# lvco-1S.net
KiCad netlist of a schematic drawn in EAGLE
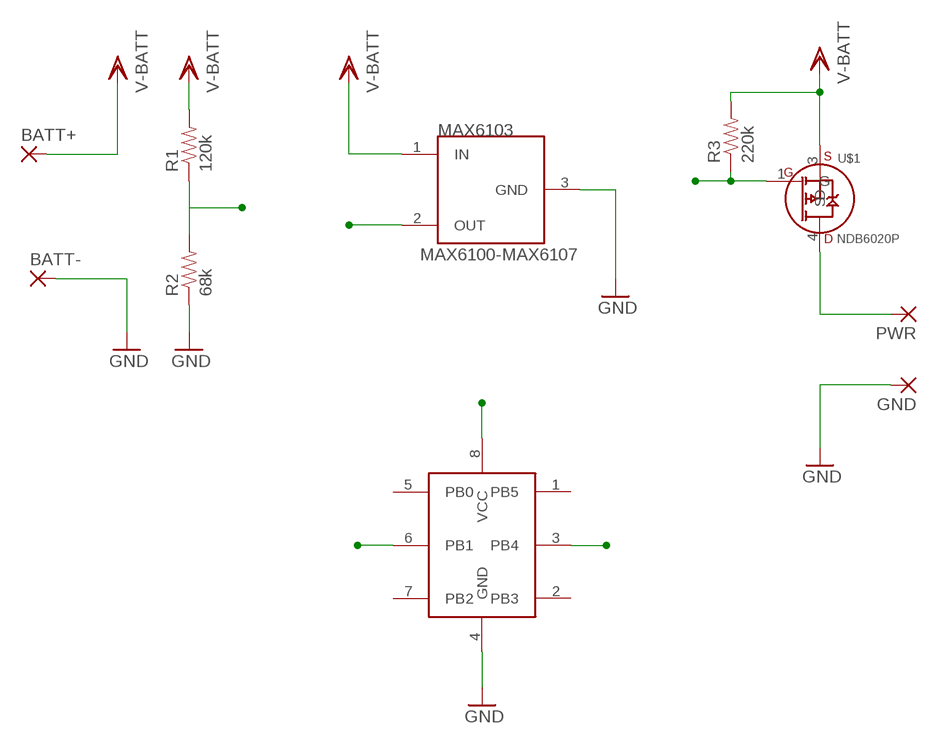
[diagram p0: schematic, sheet 1]

(export (version "E")
  (design (tool "Eeschema 10.0.6"))
  (components
    (comp (ref "BATT+")
      (value "WIREPAD2,54/1,1")
      (footprint "eagle-import:2,54_1,1")
      (libsource (lib "eagle-import") (part "WIREPAD2,54/1,1"))
    )
    (comp (ref "BATT-")
      (value "WIREPAD2,54/1,1")
      (footprint "eagle-import:2,54_1,1")
      (libsource (lib "eagle-import") (part "WIREPAD2,54/1,1"))
    )
    (comp (ref "GND")
      (value "WIREPAD2,54/1,1")
      (footprint "eagle-import:2,54_1,1")
      (libsource (lib "eagle-import") (part "WIREPAD2,54/1,1"))
    )
    (comp (ref "MAX6103")
      (value "MAX6100-MAX6107")
      (footprint "eagle-import:SOT-23-3")
      (libsource (lib "eagle-import") (part "MAX6100-MAX6107"))
    )
    (comp (ref "PWR")
      (value "WIREPAD2,54/1,1")
      (footprint "eagle-import:2,54_1,1")
      (libsource (lib "eagle-import") (part "WIREPAD2,54/1,1"))
    )
    (comp (ref "R1")
      (value "120k")
      (footprint "eagle-import:0805")
      (libsource (lib "eagle-import") (part "RESISTOR0805-RES"))
    )
    (comp (ref "R2")
      (value "68k")
      (footprint "eagle-import:0805")
      (libsource (lib "eagle-import") (part "RESISTOR0805-RES"))
    )
    (comp (ref "R3")
      (value "220k")
      (footprint "eagle-import:0805")
      (libsource (lib "eagle-import") (part "RESISTOR0805-RES"))
    )
    (comp (ref "U$1")
      (value "NDB6020P")
      (footprint "eagle-import:TO-263AB")
      (libsource (lib "eagle-import") (part "NDB6020P"))
    )
    (comp (ref "U$2")
      (value "ATTINY13")
      (footprint "eagle-import:WSOIC-8")
      (libsource (lib "eagle-import") (part "ATTINY13"))
    )
  )
  (nets
    (net (code "1") (name "/REF-BATT") (class "Default")
      (node (ref "R1") (pin "1") (pinfunction "1_1") (pintype "passive"))
      (node (ref "R2") (pin "2") (pinfunction "2_2") (pintype "passive"))
      (node (ref "U$2") (pin "6") (pinfunction "PB1_6") (pintype "bidirectional"))
    )
    (net (code "2") (name "/SW") (class "Default")
      (node (ref "R3") (pin "1") (pinfunction "1_1") (pintype "passive"))
      (node (ref "U$1") (pin "1") (pinfunction "G_1") (pintype "bidirectional"))
      (node (ref "U$2") (pin "3") (pinfunction "PB4_3") (pintype "bidirectional"))
    )
    (net (code "3") (name "/VCC") (class "Default")
      (node (ref "MAX6103") (pin "2") (pinfunction "OUT_2") (pintype "bidirectional"))
      (node (ref "U$2") (pin "8") (pinfunction "VCC_8") (pintype "bidirectional"))
    )
    (net (code "4") (name "GND") (class "Default")
      (node (ref "BATT-") (pin "1") (pinfunction "P_1") (pintype "passive"))
      (node (ref "GND") (pin "1") (pinfunction "P_1") (pintype "passive"))
      (node (ref "MAX6103") (pin "3") (pinfunction "GND_3") (pintype "bidirectional"))
      (node (ref "R2") (pin "1") (pinfunction "1_1") (pintype "passive"))
      (node (ref "U$2") (pin "4") (pinfunction "GND_4") (pintype "bidirectional"))
    )
    (net (code "5") (name "Net-(PWR-P)") (class "Default")
      (node (ref "PWR") (pin "1") (pinfunction "P_1") (pintype "passive"))
      (node (ref "U$1") (pin "4") (pinfunction "D_4") (pintype "bidirectional"))
    )
    (net (code "6") (name "V-BATT") (class "Default")
      (node (ref "BATT+") (pin "1") (pinfunction "P_1") (pintype "passive"))
      (node (ref "MAX6103") (pin "1") (pinfunction "IN_1") (pintype "bidirectional"))
      (node (ref "R1") (pin "2") (pinfunction "2_2") (pintype "passive"))
      (node (ref "R3") (pin "2") (pinfunction "2_2") (pintype "passive"))
      (node (ref "U$1") (pin "3") (pinfunction "S_3") (pintype "bidirectional"))
    )
    (net (code "7") (name "unconnected-(U$2-PB0-Pad5)") (class "Default")
      (node (ref "U$2") (pin "5") (pinfunction "PB0_5") (pintype "bidirectional"))
    )
    (net (code "8") (name "unconnected-(U$2-PB2-Pad7)") (class "Default")
      (node (ref "U$2") (pin "7") (pinfunction "PB2_7") (pintype "bidirectional"))
    )
    (net (code "9") (name "unconnected-(U$2-PB3-Pad2)") (class "Default")
      (node (ref "U$2") (pin "2") (pinfunction "PB3_2") (pintype "bidirectional"))
    )
    (net (code "10") (name "unconnected-(U$2-PB5-Pad1)") (class "Default")
      (node (ref "U$2") (pin "1") (pinfunction "PB5_1") (pintype "bidirectional"))
    )
  )
)
